# SimulatorT2PowerRevC.net
KiCad netlist of a schematic drawn in EAGLE
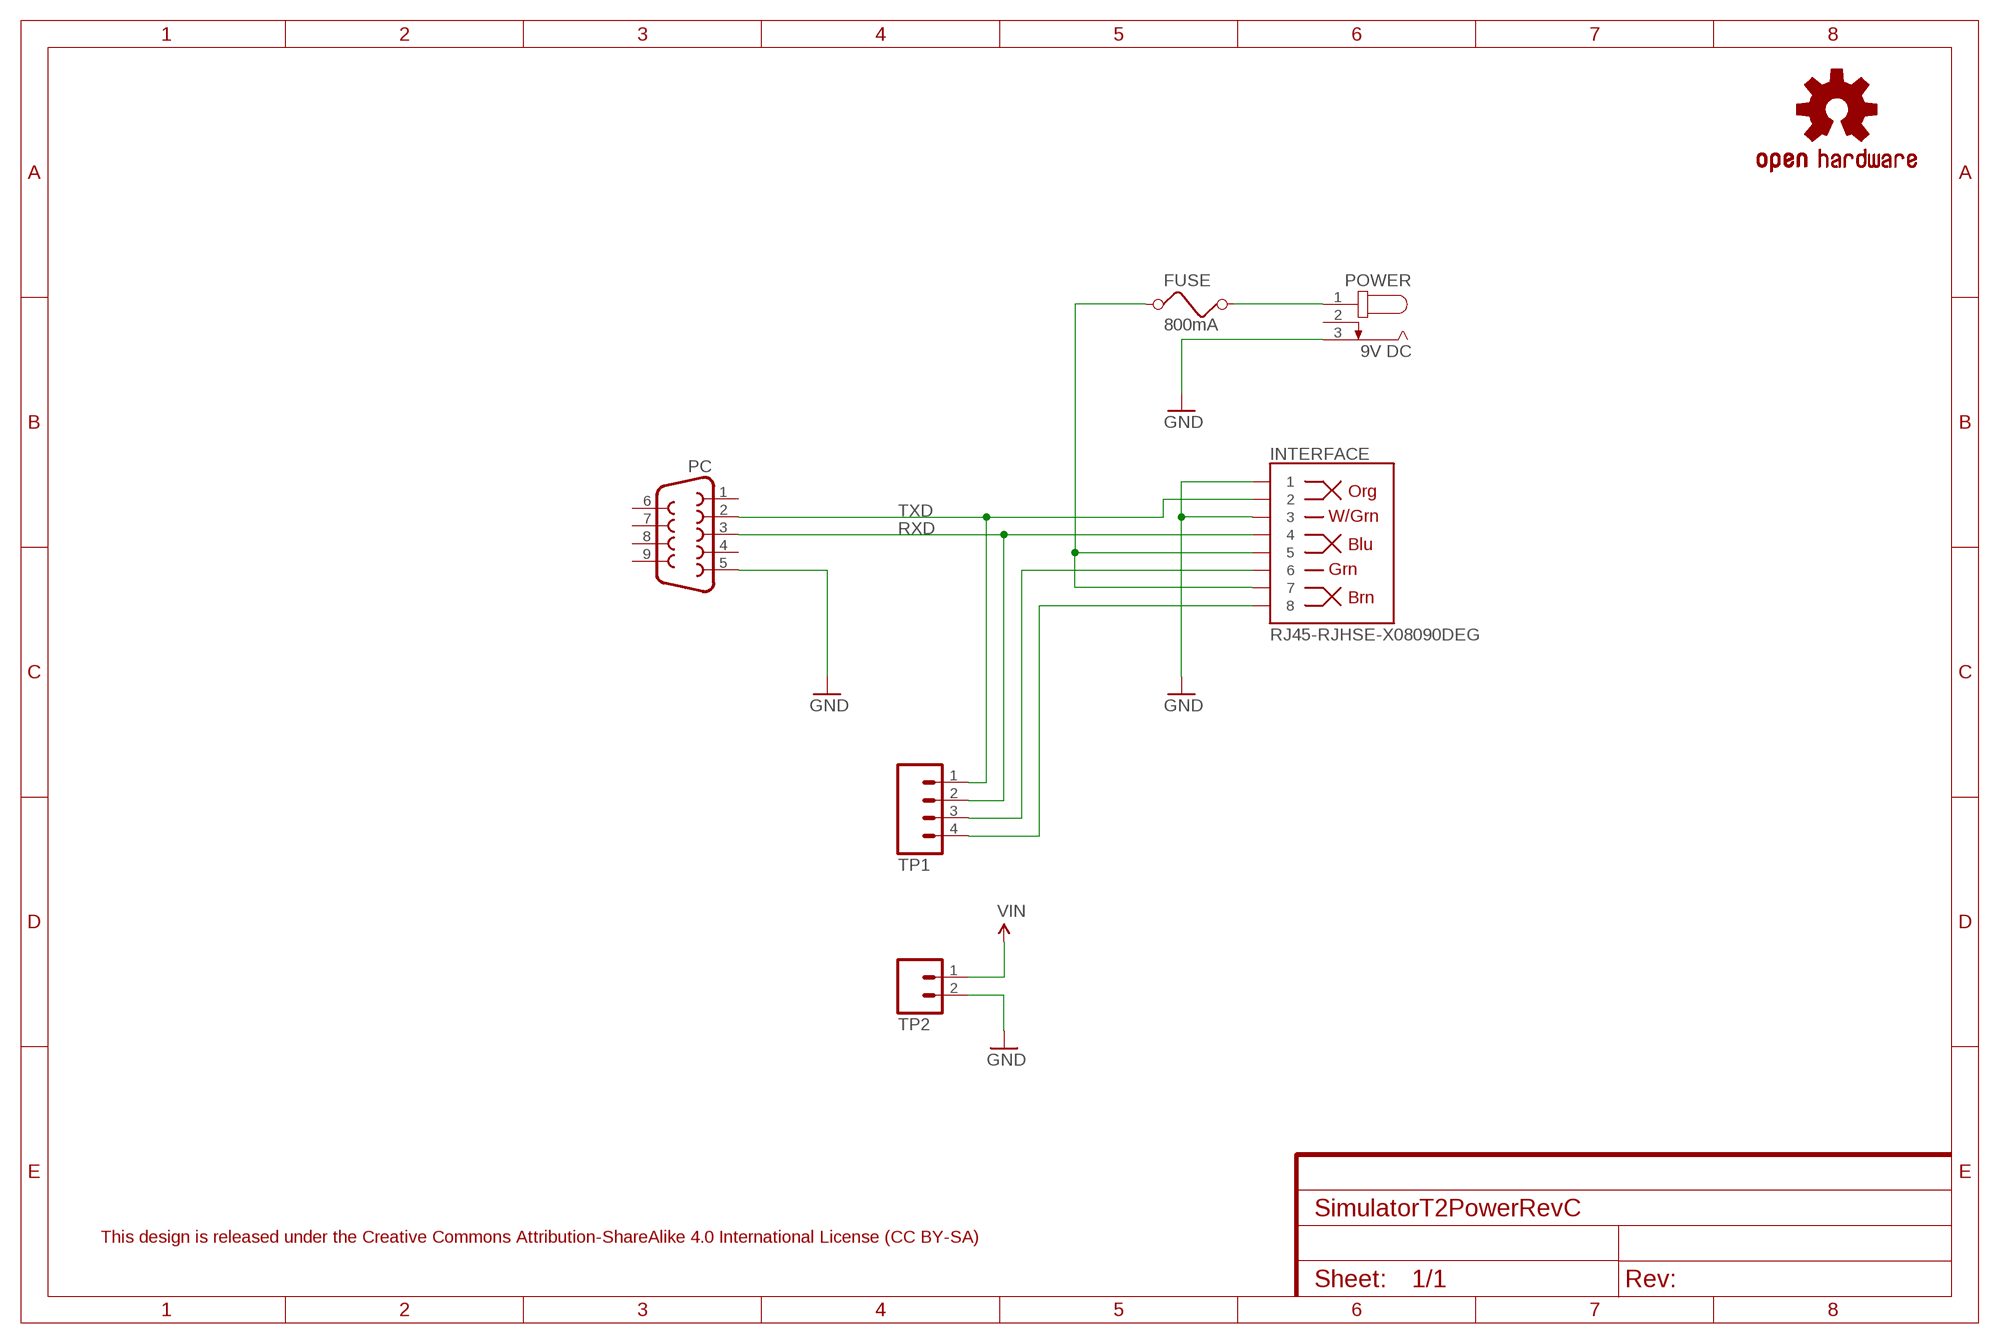
[diagram p0: schematic, sheet 1]

(export (version "E")
  (design (tool "Eeschema 10.0.6"))
  (components
    (comp (ref "FUSE")
      (value "800mA")
      (footprint "eagle-import:MCOMP-FUSE-HOLDER-PCB")
      (libsource (lib "eagle-import") (part "FUSE-HOLDER-PCB"))
    )
    (comp (ref "INTERFACE")
      (value "RJ45-RJHSE-X08090DEG")
      (footprint "eagle-import:RJ45-RJHSE-5080")
      (libsource (lib "eagle-import") (part "RJ45-RJHSE-X08090DEG"))
    )
    (comp (ref "LOGO1")
      (value "OSHW-LOGOS")
      (footprint "eagle-import:OSHW-LOGO-S")
      (libsource (lib "eagle-import") (part "OSHW-LOGOS"))
    )
    (comp (ref "PC")
      (value "DB9-CONNECTOR-PCBFEMALE")
      (footprint "eagle-import:MULTICOMP-DB9-FEMALE-PCB-90DEG")
      (libsource (lib "eagle-import") (part "DB9-CONNECTOR-PCBFEMALE"))
    )
    (comp (ref "POWER")
      (value "9V DC")
      (footprint "eagle-import:CLIFF-FC681465P-DC-JACK")
      (libsource (lib "eagle-import") (part "DC-POWER-JACK-PCB"))
    )
    (comp (ref "TP1")
      (value "M04PTH")
      (footprint "eagle-import:1X04")
      (libsource (lib "eagle-import") (part "M04PTH"))
    )
    (comp (ref "TP2")
      (value "M02PTH")
      (footprint "eagle-import:1X02")
      (libsource (lib "eagle-import") (part "M02PTH"))
    )
  )
  (nets
    (net (code "1") (name "/RXD") (class "Default")
      (node (ref "INTERFACE") (pin "4") (pinfunction "4_4") (pintype "bidirectional"))
      (node (ref "PC") (pin "3") (pinfunction "3_3") (pintype "passive"))
      (node (ref "TP1") (pin "2") (pinfunction "2_2") (pintype "passive"))
    )
    (net (code "2") (name "/TXD") (class "Default")
      (node (ref "INTERFACE") (pin "2") (pinfunction "2_2") (pintype "bidirectional"))
      (node (ref "PC") (pin "2") (pinfunction "2_2") (pintype "passive"))
      (node (ref "TP1") (pin "1") (pinfunction "1_1") (pintype "passive"))
    )
    (net (code "3") (name "GND") (class "Default")
      (node (ref "INTERFACE") (pin "1") (pinfunction "1_1") (pintype "bidirectional"))
      (node (ref "INTERFACE") (pin "3") (pinfunction "3_3") (pintype "bidirectional"))
      (node (ref "PC") (pin "5") (pinfunction "5_5") (pintype "passive"))
      (node (ref "POWER") (pin "3") (pinfunction "3_3") (pintype "passive"))
      (node (ref "TP2") (pin "2") (pinfunction "2_2") (pintype "passive"))
    )
    (net (code "4") (name "Net-(FUSE-Pad1)") (class "Default")
      (node (ref "FUSE") (pin "1") (pinfunction "1_1") (pintype "passive"))
      (node (ref "INTERFACE") (pin "5") (pinfunction "5_5") (pintype "bidirectional"))
      (node (ref "INTERFACE") (pin "7") (pinfunction "7_7") (pintype "bidirectional"))
    )
    (net (code "5") (name "Net-(INTERFACE-Pad6)") (class "Default")
      (node (ref "INTERFACE") (pin "6") (pinfunction "6_6") (pintype "bidirectional"))
      (node (ref "TP1") (pin "3") (pinfunction "3_3") (pintype "passive"))
    )
    (net (code "6") (name "Net-(INTERFACE-Pad8)") (class "Default")
      (node (ref "INTERFACE") (pin "8") (pinfunction "8_8") (pintype "bidirectional"))
      (node (ref "TP1") (pin "4") (pinfunction "4_4") (pintype "passive"))
    )
    (net (code "7") (name "VIN") (class "Default")
      (node (ref "FUSE") (pin "2") (pinfunction "2_2") (pintype "passive"))
      (node (ref "POWER") (pin "1") (pinfunction "1_1") (pintype "passive"))
      (node (ref "TP2") (pin "1") (pinfunction "1_1") (pintype "passive"))
    )
    (net (code "8") (name "unconnected-(PC-Pad1)") (class "Default")
      (node (ref "PC") (pin "1") (pinfunction "1_1") (pintype "passive"))
    )
    (net (code "9") (name "unconnected-(PC-Pad4)") (class "Default")
      (node (ref "PC") (pin "4") (pinfunction "4_4") (pintype "passive"))
    )
    (net (code "10") (name "unconnected-(PC-Pad6)") (class "Default")
      (node (ref "PC") (pin "6") (pinfunction "6_6") (pintype "passive"))
    )
    (net (code "11") (name "unconnected-(PC-Pad7)") (class "Default")
      (node (ref "PC") (pin "7") (pinfunction "7_7") (pintype "passive"))
    )
    (net (code "12") (name "unconnected-(PC-Pad8)") (class "Default")
      (node (ref "PC") (pin "8") (pinfunction "8_8") (pintype "passive"))
    )
    (net (code "13") (name "unconnected-(PC-Pad9)") (class "Default")
      (node (ref "PC") (pin "9") (pinfunction "9_9") (pintype "passive"))
    )
    (net (code "14") (name "unconnected-(POWER-Pad2)") (class "Default")
      (node (ref "POWER") (pin "2") (pinfunction "2_2") (pintype "passive"))
    )
  )
)
